# eib-64-large-stim-cutout.net
KiCad netlist of a schematic drawn in EAGLE
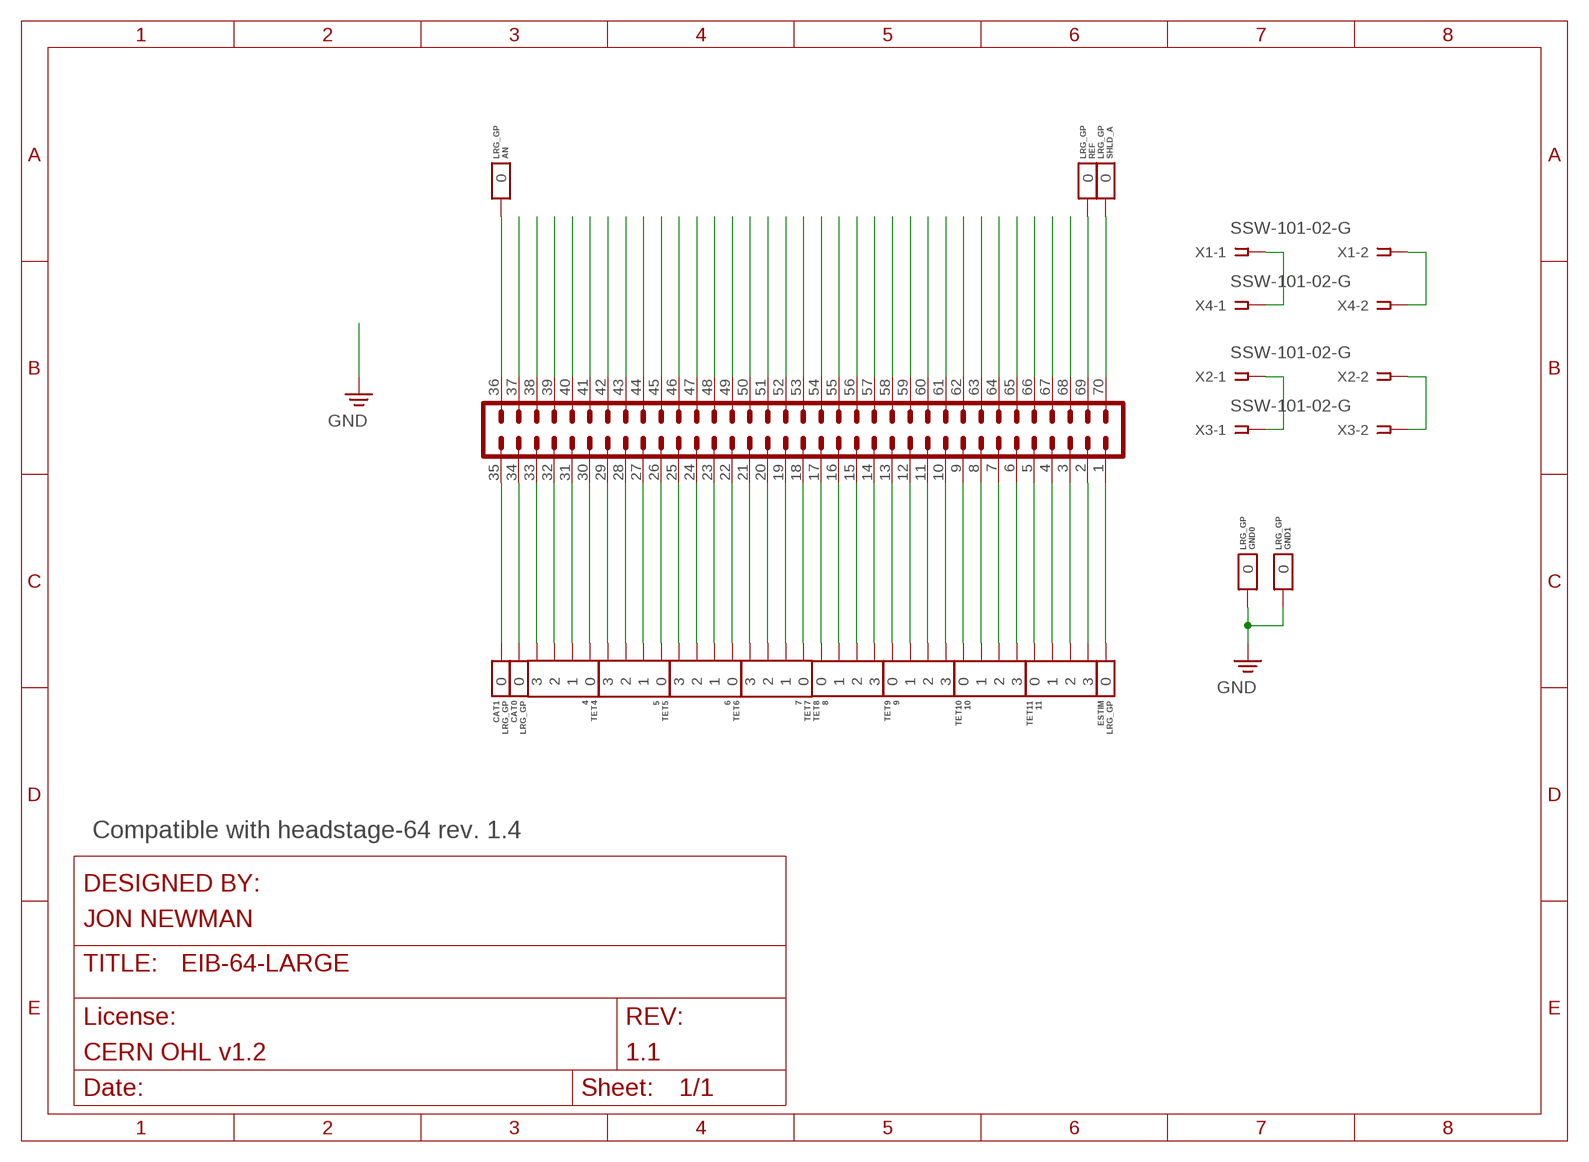
[diagram p0: schematic, sheet 1]

(export (version "E")
  (design (tool "Eeschema 10.0.6"))
  (components
    (comp (ref "AN")
      (value "LRG_GP")
      (footprint "eagle-import:GOLDPIN_0.5ID_0.7OD")
      (libsource (lib "eagle-import") (part "GOLDPIN_0.5ID_0.7OD"))
    )
    (comp (ref "CAT0")
      (value "LRG_GP")
      (footprint "eagle-import:GOLDPIN_0.5ID_0.7OD")
      (libsource (lib "eagle-import") (part "GOLDPIN_0.5ID_0.7OD"))
    )
    (comp (ref "CAT1")
      (value "LRG_GP")
      (footprint "eagle-import:GOLDPIN_0.5ID_0.7OD")
      (libsource (lib "eagle-import") (part "GOLDPIN_0.5ID_0.7OD"))
    )
    (comp (ref "ESTIM")
      (value "LRG_GP")
      (footprint "eagle-import:GOLDPIN_0.5ID_0.7OD")
      (libsource (lib "eagle-import") (part "GOLDPIN_0.5ID_0.7OD"))
    )
    (comp (ref "GND0")
      (value "LRG_GP")
      (footprint "eagle-import:GOLDPIN_0.5ID_0.7OD")
      (libsource (lib "eagle-import") (part "GOLDPIN_0.5ID_0.7OD"))
    )
    (comp (ref "GND1")
      (value "LRG_GP")
      (footprint "eagle-import:GOLDPIN_0.5ID_0.7OD")
      (libsource (lib "eagle-import") (part "GOLDPIN_0.5ID_0.7OD"))
    )
    (comp (ref "J1")
      (value "DF40-REC")
      (footprint "eagle-import:DDF40-70REC-LRG")
      (libsource (lib "eagle-import") (part "PINHD-2X35_DF40REF-LRG"))
    )
    (comp (ref "REF")
      (value "LRG_GP")
      (footprint "eagle-import:GOLDPIN_0.5ID_0.7OD")
      (libsource (lib "eagle-import") (part "GOLDPIN_0.5ID_0.7OD"))
    )
    (comp (ref "SHLD_A")
      (value "LRG_GP")
      (footprint "eagle-import:GOLDPIN_0.5ID_0.7OD")
      (libsource (lib "eagle-import") (part "GOLDPIN_0.5ID_0.7OD"))
    )
    (comp (ref "TET4")
      (value "4")
      (footprint "eagle-import:TETRODE_128_0.5ID_0.7OD")
      (libsource (lib "eagle-import") (part "TETRODE_128_0.5ID_0.7OD"))
    )
    (comp (ref "TET5")
      (value "5")
      (footprint "eagle-import:TETRODE_128_0.5ID_0.7OD")
      (libsource (lib "eagle-import") (part "TETRODE_128_0.5ID_0.7OD"))
    )
    (comp (ref "TET6")
      (value "6")
      (footprint "eagle-import:TETRODE_128_0.5ID_0.7OD")
      (libsource (lib "eagle-import") (part "TETRODE_128_0.5ID_0.7OD"))
    )
    (comp (ref "TET7")
      (value "7")
      (footprint "eagle-import:TETRODE_128_0.5ID_0.7OD")
      (libsource (lib "eagle-import") (part "TETRODE_128_0.5ID_0.7OD"))
    )
    (comp (ref "TET8")
      (value "8")
      (footprint "eagle-import:TETRODE_128_0.5ID_0.7OD")
      (libsource (lib "eagle-import") (part "TETRODE_128_0.5ID_0.7OD"))
    )
    (comp (ref "TET9")
      (value "9")
      (footprint "eagle-import:TETRODE_128_0.5ID_0.7OD")
      (libsource (lib "eagle-import") (part "TETRODE_128_0.5ID_0.7OD"))
    )
    (comp (ref "TET10")
      (value "10")
      (footprint "eagle-import:TETRODE_128_0.5ID_0.7OD")
      (libsource (lib "eagle-import") (part "TETRODE_128_0.5ID_0.7OD"))
    )
    (comp (ref "TET11")
      (value "11")
      (footprint "eagle-import:TETRODE_128_0.5ID_0.7OD")
      (libsource (lib "eagle-import") (part "TETRODE_128_0.5ID_0.7OD"))
    )
    (comp (ref "X1")
      (value "SSW-101-02-G")
      (footprint "eagle-import:SSW-101-02-G-D-50MIL")
      (libsource (lib "eagle-import") (part "SSW-101-02-G"))
    )
    (comp (ref "X2")
      (value "SSW-101-02-G")
      (footprint "eagle-import:SSW-101-02-G-D-50MIL")
      (libsource (lib "eagle-import") (part "SSW-101-02-G"))
    )
    (comp (ref "X3")
      (value "SSW-101-02-G")
      (footprint "eagle-import:SSW-101-02-G-D-50MIL")
      (libsource (lib "eagle-import") (part "SSW-101-02-G"))
    )
    (comp (ref "X4")
      (value "SSW-101-02-G")
      (footprint "eagle-import:SSW-101-02-G-D-50MIL")
      (libsource (lib "eagle-import") (part "SSW-101-02-G"))
    )
  )
  (nets
    (net (code "1") (name "GND") (class "Default")
      (node (ref "GND0") (pin "P$1") (pinfunction "0_P$1") (pintype "bidirectional"))
      (node (ref "GND1") (pin "P$1") (pinfunction "0_P$1") (pintype "bidirectional"))
    )
    (net (code "2") (name "Net-(AN-0)") (class "Default")
      (node (ref "AN") (pin "P$1") (pinfunction "0_P$1") (pintype "bidirectional"))
      (node (ref "J1") (pin "36") (pinfunction "36_36") (pintype "bidirectional"))
    )
    (net (code "3") (name "Net-(CAT0-0)") (class "Default")
      (node (ref "CAT0") (pin "P$1") (pinfunction "0_P$1") (pintype "bidirectional"))
      (node (ref "J1") (pin "34") (pinfunction "34_34") (pintype "bidirectional"))
    )
    (net (code "4") (name "Net-(CAT1-0)") (class "Default")
      (node (ref "CAT1") (pin "P$1") (pinfunction "0_P$1") (pintype "bidirectional"))
      (node (ref "J1") (pin "35") (pinfunction "35_35") (pintype "bidirectional"))
    )
    (net (code "5") (name "Net-(ESTIM-0)") (class "Default")
      (node (ref "ESTIM") (pin "P$1") (pinfunction "0_P$1") (pintype "bidirectional"))
      (node (ref "J1") (pin "1") (pinfunction "1_1") (pintype "bidirectional"))
    )
    (net (code "6") (name "Net-(J1-Pad2)") (class "Default")
      (node (ref "J1") (pin "2") (pinfunction "2_2") (pintype "bidirectional"))
      (node (ref "TET11") (pin "3") (pinfunction "3_3") (pintype "bidirectional"))
    )
    (net (code "7") (name "Net-(J1-Pad3)") (class "Default")
      (node (ref "J1") (pin "3") (pinfunction "3_3") (pintype "bidirectional"))
      (node (ref "TET11") (pin "2") (pinfunction "2_2") (pintype "bidirectional"))
    )
    (net (code "8") (name "Net-(J1-Pad4)") (class "Default")
      (node (ref "J1") (pin "4") (pinfunction "4_4") (pintype "bidirectional"))
      (node (ref "TET11") (pin "1") (pinfunction "1_1") (pintype "bidirectional"))
    )
    (net (code "9") (name "Net-(J1-Pad5)") (class "Default")
      (node (ref "J1") (pin "5") (pinfunction "5_5") (pintype "bidirectional"))
      (node (ref "TET11") (pin "0") (pinfunction "0_0") (pintype "bidirectional"))
    )
    (net (code "10") (name "Net-(J1-Pad6)") (class "Default")
      (node (ref "J1") (pin "6") (pinfunction "6_6") (pintype "bidirectional"))
      (node (ref "TET10") (pin "3") (pinfunction "3_3") (pintype "bidirectional"))
    )
    (net (code "11") (name "Net-(J1-Pad7)") (class "Default")
      (node (ref "J1") (pin "7") (pinfunction "7_7") (pintype "bidirectional"))
      (node (ref "TET10") (pin "2") (pinfunction "2_2") (pintype "bidirectional"))
    )
    (net (code "12") (name "Net-(J1-Pad8)") (class "Default")
      (node (ref "J1") (pin "8") (pinfunction "8_8") (pintype "bidirectional"))
      (node (ref "TET10") (pin "1") (pinfunction "1_1") (pintype "bidirectional"))
    )
    (net (code "13") (name "Net-(J1-Pad9)") (class "Default")
      (node (ref "J1") (pin "9") (pinfunction "9_9") (pintype "bidirectional"))
      (node (ref "TET10") (pin "0") (pinfunction "0_0") (pintype "bidirectional"))
    )
    (net (code "14") (name "Net-(J1-Pad10)") (class "Default")
      (node (ref "J1") (pin "10") (pinfunction "10_10") (pintype "bidirectional"))
      (node (ref "TET9") (pin "3") (pinfunction "3_3") (pintype "bidirectional"))
    )
    (net (code "15") (name "Net-(J1-Pad11)") (class "Default")
      (node (ref "J1") (pin "11") (pinfunction "11_11") (pintype "bidirectional"))
      (node (ref "TET9") (pin "2") (pinfunction "2_2") (pintype "bidirectional"))
    )
    (net (code "16") (name "Net-(J1-Pad12)") (class "Default")
      (node (ref "J1") (pin "12") (pinfunction "12_12") (pintype "bidirectional"))
      (node (ref "TET9") (pin "1") (pinfunction "1_1") (pintype "bidirectional"))
    )
    (net (code "17") (name "Net-(J1-Pad13)") (class "Default")
      (node (ref "J1") (pin "13") (pinfunction "13_13") (pintype "bidirectional"))
      (node (ref "TET9") (pin "0") (pinfunction "0_0") (pintype "bidirectional"))
    )
    (net (code "18") (name "Net-(J1-Pad14)") (class "Default")
      (node (ref "J1") (pin "14") (pinfunction "14_14") (pintype "bidirectional"))
      (node (ref "TET8") (pin "3") (pinfunction "3_3") (pintype "bidirectional"))
    )
    (net (code "19") (name "Net-(J1-Pad15)") (class "Default")
      (node (ref "J1") (pin "15") (pinfunction "15_15") (pintype "bidirectional"))
      (node (ref "TET8") (pin "2") (pinfunction "2_2") (pintype "bidirectional"))
    )
    (net (code "20") (name "Net-(J1-Pad16)") (class "Default")
      (node (ref "J1") (pin "16") (pinfunction "16_16") (pintype "bidirectional"))
      (node (ref "TET8") (pin "1") (pinfunction "1_1") (pintype "bidirectional"))
    )
    (net (code "21") (name "Net-(J1-Pad17)") (class "Default")
      (node (ref "J1") (pin "17") (pinfunction "17_17") (pintype "bidirectional"))
      (node (ref "TET8") (pin "0") (pinfunction "0_0") (pintype "bidirectional"))
    )
    (net (code "22") (name "Net-(J1-Pad18)") (class "Default")
      (node (ref "J1") (pin "18") (pinfunction "18_18") (pintype "bidirectional"))
      (node (ref "TET7") (pin "0") (pinfunction "0_0") (pintype "bidirectional"))
    )
    (net (code "23") (name "Net-(J1-Pad19)") (class "Default")
      (node (ref "J1") (pin "19") (pinfunction "19_19") (pintype "bidirectional"))
      (node (ref "TET7") (pin "1") (pinfunction "1_1") (pintype "bidirectional"))
    )
    (net (code "24") (name "Net-(J1-Pad20)") (class "Default")
      (node (ref "J1") (pin "20") (pinfunction "20_20") (pintype "bidirectional"))
      (node (ref "TET7") (pin "2") (pinfunction "2_2") (pintype "bidirectional"))
    )
    (net (code "25") (name "Net-(J1-Pad21)") (class "Default")
      (node (ref "J1") (pin "21") (pinfunction "21_21") (pintype "bidirectional"))
      (node (ref "TET7") (pin "3") (pinfunction "3_3") (pintype "bidirectional"))
    )
    (net (code "26") (name "Net-(J1-Pad22)") (class "Default")
      (node (ref "J1") (pin "22") (pinfunction "22_22") (pintype "bidirectional"))
      (node (ref "TET6") (pin "0") (pinfunction "0_0") (pintype "bidirectional"))
    )
    (net (code "27") (name "Net-(J1-Pad23)") (class "Default")
      (node (ref "J1") (pin "23") (pinfunction "23_23") (pintype "bidirectional"))
      (node (ref "TET6") (pin "1") (pinfunction "1_1") (pintype "bidirectional"))
    )
    (net (code "28") (name "Net-(J1-Pad24)") (class "Default")
      (node (ref "J1") (pin "24") (pinfunction "24_24") (pintype "bidirectional"))
      (node (ref "TET6") (pin "2") (pinfunction "2_2") (pintype "bidirectional"))
    )
    (net (code "29") (name "Net-(J1-Pad25)") (class "Default")
      (node (ref "J1") (pin "25") (pinfunction "25_25") (pintype "bidirectional"))
      (node (ref "TET6") (pin "3") (pinfunction "3_3") (pintype "bidirectional"))
    )
    (net (code "30") (name "Net-(J1-Pad26)") (class "Default")
      (node (ref "J1") (pin "26") (pinfunction "26_26") (pintype "bidirectional"))
      (node (ref "TET5") (pin "0") (pinfunction "0_0") (pintype "bidirectional"))
    )
    (net (code "31") (name "Net-(J1-Pad27)") (class "Default")
      (node (ref "J1") (pin "27") (pinfunction "27_27") (pintype "bidirectional"))
      (node (ref "TET5") (pin "1") (pinfunction "1_1") (pintype "bidirectional"))
    )
    (net (code "32") (name "Net-(J1-Pad28)") (class "Default")
      (node (ref "J1") (pin "28") (pinfunction "28_28") (pintype "bidirectional"))
      (node (ref "TET5") (pin "2") (pinfunction "2_2") (pintype "bidirectional"))
    )
    (net (code "33") (name "Net-(J1-Pad29)") (class "Default")
      (node (ref "J1") (pin "29") (pinfunction "29_29") (pintype "bidirectional"))
      (node (ref "TET5") (pin "3") (pinfunction "3_3") (pintype "bidirectional"))
    )
    (net (code "34") (name "Net-(J1-Pad30)") (class "Default")
      (node (ref "J1") (pin "30") (pinfunction "30_30") (pintype "bidirectional"))
      (node (ref "TET4") (pin "0") (pinfunction "0_0") (pintype "bidirectional"))
    )
    (net (code "35") (name "Net-(J1-Pad31)") (class "Default")
      (node (ref "J1") (pin "31") (pinfunction "31_31") (pintype "bidirectional"))
      (node (ref "TET4") (pin "1") (pinfunction "1_1") (pintype "bidirectional"))
    )
    (net (code "36") (name "Net-(J1-Pad32)") (class "Default")
      (node (ref "J1") (pin "32") (pinfunction "32_32") (pintype "bidirectional"))
      (node (ref "TET4") (pin "2") (pinfunction "2_2") (pintype "bidirectional"))
    )
    (net (code "37") (name "Net-(J1-Pad33)") (class "Default")
      (node (ref "J1") (pin "33") (pinfunction "33_33") (pintype "bidirectional"))
      (node (ref "TET4") (pin "3") (pinfunction "3_3") (pintype "bidirectional"))
    )
    (net (code "38") (name "Net-(REF-0)") (class "Default")
      (node (ref "J1") (pin "69") (pinfunction "69_69") (pintype "bidirectional"))
      (node (ref "REF") (pin "P$1") (pinfunction "0_P$1") (pintype "bidirectional"))
    )
    (net (code "39") (name "Net-(SHLD_A-0)") (class "Default")
      (node (ref "J1") (pin "70") (pinfunction "70_70") (pintype "bidirectional"))
      (node (ref "SHLD_A") (pin "P$1") (pinfunction "0_P$1") (pintype "bidirectional"))
    )
    (net (code "40") (name "Net-(X1-Pad1)") (class "Default")
      (node (ref "X1") (pin "1") (pinfunction "1_1") (pintype "passive"))
      (node (ref "X4") (pin "1") (pinfunction "1_1") (pintype "passive"))
    )
    (net (code "41") (name "Net-(X1B-1)") (class "Default")
      (node (ref "X1") (pin "2") (pinfunction "1_2") (pintype "passive"))
      (node (ref "X4") (pin "2") (pinfunction "1_2") (pintype "passive"))
    )
    (net (code "42") (name "Net-(X2-Pad1)") (class "Default")
      (node (ref "X2") (pin "1") (pinfunction "1_1") (pintype "passive"))
      (node (ref "X3") (pin "1") (pinfunction "1_1") (pintype "passive"))
    )
    (net (code "43") (name "Net-(X2B-1)") (class "Default")
      (node (ref "X2") (pin "2") (pinfunction "1_2") (pintype "passive"))
      (node (ref "X3") (pin "2") (pinfunction "1_2") (pintype "passive"))
    )
    (net (code "44") (name "unconnected-(J1-Pad37)") (class "Default")
      (node (ref "J1") (pin "37") (pinfunction "37_37") (pintype "bidirectional"))
    )
    (net (code "45") (name "unconnected-(J1-Pad38)") (class "Default")
      (node (ref "J1") (pin "38") (pinfunction "38_38") (pintype "bidirectional"))
    )
    (net (code "46") (name "unconnected-(J1-Pad39)") (class "Default")
      (node (ref "J1") (pin "39") (pinfunction "39_39") (pintype "bidirectional"))
    )
    (net (code "47") (name "unconnected-(J1-Pad40)") (class "Default")
      (node (ref "J1") (pin "40") (pinfunction "40_40") (pintype "bidirectional"))
    )
    (net (code "48") (name "unconnected-(J1-Pad41)") (class "Default")
      (node (ref "J1") (pin "41") (pinfunction "41_41") (pintype "bidirectional"))
    )
    (net (code "49") (name "unconnected-(J1-Pad42)") (class "Default")
      (node (ref "J1") (pin "42") (pinfunction "42_42") (pintype "bidirectional"))
    )
    (net (code "50") (name "unconnected-(J1-Pad43)") (class "Default")
      (node (ref "J1") (pin "43") (pinfunction "43_43") (pintype "bidirectional"))
    )
    (net (code "51") (name "unconnected-(J1-Pad44)") (class "Default")
      (node (ref "J1") (pin "44") (pinfunction "44_44") (pintype "bidirectional"))
    )
    (net (code "52") (name "unconnected-(J1-Pad45)") (class "Default")
      (node (ref "J1") (pin "45") (pinfunction "45_45") (pintype "bidirectional"))
    )
    (net (code "53") (name "unconnected-(J1-Pad46)") (class "Default")
      (node (ref "J1") (pin "46") (pinfunction "46_46") (pintype "bidirectional"))
    )
    (net (code "54") (name "unconnected-(J1-Pad47)") (class "Default")
      (node (ref "J1") (pin "47") (pinfunction "47_47") (pintype "bidirectional"))
    )
    (net (code "55") (name "unconnected-(J1-Pad48)") (class "Default")
      (node (ref "J1") (pin "48") (pinfunction "48_48") (pintype "bidirectional"))
    )
    (net (code "56") (name "unconnected-(J1-Pad49)") (class "Default")
      (node (ref "J1") (pin "49") (pinfunction "49_49") (pintype "bidirectional"))
    )
    (net (code "57") (name "unconnected-(J1-Pad50)") (class "Default")
      (node (ref "J1") (pin "50") (pinfunction "50_50") (pintype "bidirectional"))
    )
    (net (code "58") (name "unconnected-(J1-Pad51)") (class "Default")
      (node (ref "J1") (pin "51") (pinfunction "51_51") (pintype "bidirectional"))
    )
    (net (code "59") (name "unconnected-(J1-Pad52)") (class "Default")
      (node (ref "J1") (pin "52") (pinfunction "52_52") (pintype "bidirectional"))
    )
    (net (code "60") (name "unconnected-(J1-Pad53)") (class "Default")
      (node (ref "J1") (pin "53") (pinfunction "53_53") (pintype "bidirectional"))
    )
    (net (code "61") (name "unconnected-(J1-Pad54)") (class "Default")
      (node (ref "J1") (pin "54") (pinfunction "54_54") (pintype "bidirectional"))
    )
    (net (code "62") (name "unconnected-(J1-Pad55)") (class "Default")
      (node (ref "J1") (pin "55") (pinfunction "55_55") (pintype "bidirectional"))
    )
    (net (code "63") (name "unconnected-(J1-Pad56)") (class "Default")
      (node (ref "J1") (pin "56") (pinfunction "56_56") (pintype "bidirectional"))
    )
    (net (code "64") (name "unconnected-(J1-Pad57)") (class "Default")
      (node (ref "J1") (pin "57") (pinfunction "57_57") (pintype "bidirectional"))
    )
    (net (code "65") (name "unconnected-(J1-Pad58)") (class "Default")
      (node (ref "J1") (pin "58") (pinfunction "58_58") (pintype "bidirectional"))
    )
    (net (code "66") (name "unconnected-(J1-Pad59)") (class "Default")
      (node (ref "J1") (pin "59") (pinfunction "59_59") (pintype "bidirectional"))
    )
    (net (code "67") (name "unconnected-(J1-Pad60)") (class "Default")
      (node (ref "J1") (pin "60") (pinfunction "60_60") (pintype "bidirectional"))
    )
    (net (code "68") (name "unconnected-(J1-Pad61)") (class "Default")
      (node (ref "J1") (pin "61") (pinfunction "61_61") (pintype "bidirectional"))
    )
    (net (code "69") (name "unconnected-(J1-Pad62)") (class "Default")
      (node (ref "J1") (pin "62") (pinfunction "62_62") (pintype "bidirectional"))
    )
    (net (code "70") (name "unconnected-(J1-Pad63)") (class "Default")
      (node (ref "J1") (pin "63") (pinfunction "63_63") (pintype "bidirectional"))
    )
    (net (code "71") (name "unconnected-(J1-Pad64)") (class "Default")
      (node (ref "J1") (pin "64") (pinfunction "64_64") (pintype "bidirectional"))
    )
    (net (code "72") (name "unconnected-(J1-Pad65)") (class "Default")
      (node (ref "J1") (pin "65") (pinfunction "65_65") (pintype "bidirectional"))
    )
    (net (code "73") (name "unconnected-(J1-Pad66)") (class "Default")
      (node (ref "J1") (pin "66") (pinfunction "66_66") (pintype "bidirectional"))
    )
    (net (code "74") (name "unconnected-(J1-Pad67)") (class "Default")
      (node (ref "J1") (pin "67") (pinfunction "67_67") (pintype "bidirectional"))
    )
    (net (code "75") (name "unconnected-(J1-Pad68)") (class "Default")
      (node (ref "J1") (pin "68") (pinfunction "68_68") (pintype "bidirectional"))
    )
  )
)
